# salo_led_pcb.net
KiCad netlist of a schematic drawn in Altium Designer
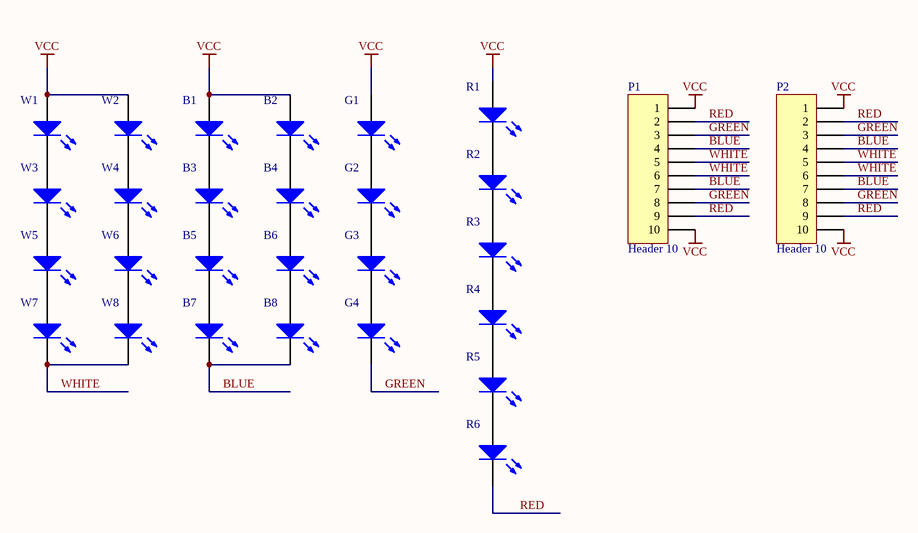
[diagram p0: salo_led_pcb.SchDoc]

(export (version "E")
  (design (tool "Eeschema 10.0.6"))
  (components
    (comp (ref "B1")
      (value "LED0")
      (footprint "1W LED")
      (description "Typical INFRARED GaAs LED")
      (libsource (lib "Miscellaneous Devices") (part "LED0"))
    )
    (comp (ref "B2")
      (value "LED0")
      (footprint "1W LED")
      (description "Typical INFRARED GaAs LED")
      (libsource (lib "Miscellaneous Devices") (part "LED0"))
    )
    (comp (ref "B3")
      (value "LED0")
      (footprint "1W LED")
      (description "Typical INFRARED GaAs LED")
      (libsource (lib "Miscellaneous Devices") (part "LED0"))
    )
    (comp (ref "B4")
      (value "LED0")
      (footprint "1W LED")
      (description "Typical INFRARED GaAs LED")
      (libsource (lib "Miscellaneous Devices") (part "LED0"))
    )
    (comp (ref "B5")
      (value "LED0")
      (footprint "1W LED")
      (description "Typical INFRARED GaAs LED")
      (libsource (lib "Miscellaneous Devices") (part "LED0"))
    )
    (comp (ref "B6")
      (value "LED0")
      (footprint "1W LED")
      (description "Typical INFRARED GaAs LED")
      (libsource (lib "Miscellaneous Devices") (part "LED0"))
    )
    (comp (ref "B7")
      (value "LED0")
      (footprint "1W LED")
      (description "Typical INFRARED GaAs LED")
      (libsource (lib "Miscellaneous Devices") (part "LED0"))
    )
    (comp (ref "B8")
      (value "LED0")
      (footprint "1W LED")
      (description "Typical INFRARED GaAs LED")
      (libsource (lib "Miscellaneous Devices") (part "LED0"))
    )
    (comp (ref "G1")
      (value "LED0")
      (footprint "1W LED")
      (description "Typical INFRARED GaAs LED")
      (libsource (lib "Miscellaneous Devices") (part "LED0"))
    )
    (comp (ref "G2")
      (value "LED0")
      (footprint "1W LED")
      (description "Typical INFRARED GaAs LED")
      (libsource (lib "Miscellaneous Devices") (part "LED0"))
    )
    (comp (ref "G3")
      (value "LED0")
      (footprint "1W LED")
      (description "Typical INFRARED GaAs LED")
      (libsource (lib "Miscellaneous Devices") (part "LED0"))
    )
    (comp (ref "G4")
      (value "LED0")
      (footprint "1W LED")
      (description "Typical INFRARED GaAs LED")
      (libsource (lib "Miscellaneous Devices") (part "LED0"))
    )
    (comp (ref "P1")
      (value "Header 10")
      (footprint "HDR1X10")
      (description "Header, 10-Pin")
      (fields (field (name "PUBLISHER") "Altium Limited"))
      (libsource (lib "Miscellaneous Connectors") (part "Header 10"))
    )
    (comp (ref "P2")
      (value "Header 10")
      (footprint "HDR1X10")
      (description "Header, 10-Pin")
      (fields (field (name "PUBLISHER") "Altium Limited"))
      (libsource (lib "Miscellaneous Connectors") (part "Header 10"))
    )
    (comp (ref "R1")
      (value "LED0")
      (footprint "1W LED")
      (description "Typical INFRARED GaAs LED")
      (libsource (lib "Miscellaneous Devices") (part "LED0"))
    )
    (comp (ref "R2")
      (value "LED0")
      (footprint "1W LED")
      (description "Typical INFRARED GaAs LED")
      (libsource (lib "Miscellaneous Devices") (part "LED0"))
    )
    (comp (ref "R3")
      (value "LED0")
      (footprint "1W LED")
      (description "Typical INFRARED GaAs LED")
      (libsource (lib "Miscellaneous Devices") (part "LED0"))
    )
    (comp (ref "R4")
      (value "LED0")
      (footprint "1W LED")
      (description "Typical INFRARED GaAs LED")
      (libsource (lib "Miscellaneous Devices") (part "LED0"))
    )
    (comp (ref "R5")
      (value "LED0")
      (footprint "1W LED")
      (description "Typical INFRARED GaAs LED")
      (libsource (lib "Miscellaneous Devices") (part "LED0"))
    )
    (comp (ref "R6")
      (value "LED0")
      (footprint "1W LED")
      (description "Typical INFRARED GaAs LED")
      (libsource (lib "Miscellaneous Devices") (part "LED0"))
    )
    (comp (ref "W1")
      (value "LED0")
      (footprint "1W LED")
      (description "Typical INFRARED GaAs LED")
      (libsource (lib "Miscellaneous Devices") (part "LED0"))
    )
    (comp (ref "W2")
      (value "LED0")
      (footprint "1W LED")
      (description "Typical INFRARED GaAs LED")
      (libsource (lib "Miscellaneous Devices") (part "LED0"))
    )
    (comp (ref "W3")
      (value "LED0")
      (footprint "1W LED")
      (description "Typical INFRARED GaAs LED")
      (libsource (lib "Miscellaneous Devices") (part "LED0"))
    )
    (comp (ref "W4")
      (value "LED0")
      (footprint "1W LED")
      (description "Typical INFRARED GaAs LED")
      (libsource (lib "Miscellaneous Devices") (part "LED0"))
    )
    (comp (ref "W5")
      (value "LED0")
      (footprint "1W LED")
      (description "Typical INFRARED GaAs LED")
      (libsource (lib "Miscellaneous Devices") (part "LED0"))
    )
    (comp (ref "W6")
      (value "LED0")
      (footprint "1W LED")
      (description "Typical INFRARED GaAs LED")
      (libsource (lib "Miscellaneous Devices") (part "LED0"))
    )
    (comp (ref "W7")
      (value "LED0")
      (footprint "1W LED")
      (description "Typical INFRARED GaAs LED")
      (libsource (lib "Miscellaneous Devices") (part "LED0"))
    )
    (comp (ref "W8")
      (value "LED0")
      (footprint "1W LED")
      (description "Typical INFRARED GaAs LED")
      (libsource (lib "Miscellaneous Devices") (part "LED0"))
    )
  )
  (nets
    (net (code "1") (name "/BLUE") (class "Default")
      (node (ref "B7") (pin "2") (pinfunction "K_2") (pintype "passive"))
      (node (ref "B8") (pin "2") (pinfunction "K_2") (pintype "passive"))
      (node (ref "P1") (pin "4") (pinfunction "4_4") (pintype "passive"))
      (node (ref "P1") (pin "7") (pinfunction "7_7") (pintype "passive"))
      (node (ref "P2") (pin "4") (pinfunction "4_4") (pintype "passive"))
      (node (ref "P2") (pin "7") (pinfunction "7_7") (pintype "passive"))
    )
    (net (code "2") (name "/GREEN") (class "Default")
      (node (ref "G4") (pin "2") (pinfunction "K_2") (pintype "passive"))
      (node (ref "P1") (pin "3") (pinfunction "3_3") (pintype "passive"))
      (node (ref "P1") (pin "8") (pinfunction "8_8") (pintype "passive"))
      (node (ref "P2") (pin "3") (pinfunction "3_3") (pintype "passive"))
      (node (ref "P2") (pin "8") (pinfunction "8_8") (pintype "passive"))
    )
    (net (code "3") (name "/RED") (class "Default")
      (node (ref "P1") (pin "2") (pinfunction "2_2") (pintype "passive"))
      (node (ref "P1") (pin "9") (pinfunction "9_9") (pintype "passive"))
      (node (ref "P2") (pin "2") (pinfunction "2_2") (pintype "passive"))
      (node (ref "P2") (pin "9") (pinfunction "9_9") (pintype "passive"))
      (node (ref "R6") (pin "2") (pinfunction "K_2") (pintype "passive"))
    )
    (net (code "4") (name "/WHITE") (class "Default")
      (node (ref "P1") (pin "5") (pinfunction "5_5") (pintype "passive"))
      (node (ref "P1") (pin "6") (pinfunction "6_6") (pintype "passive"))
      (node (ref "P2") (pin "5") (pinfunction "5_5") (pintype "passive"))
      (node (ref "P2") (pin "6") (pinfunction "6_6") (pintype "passive"))
      (node (ref "W7") (pin "2") (pinfunction "K_2") (pintype "passive"))
      (node (ref "W8") (pin "2") (pinfunction "K_2") (pintype "passive"))
    )
    (net (code "5") (name "Net-(B1-K)") (class "Default")
      (node (ref "B1") (pin "2") (pinfunction "K_2") (pintype "passive"))
      (node (ref "B3") (pin "1") (pinfunction "A_1") (pintype "passive"))
    )
    (net (code "6") (name "Net-(B2-K)") (class "Default")
      (node (ref "B2") (pin "2") (pinfunction "K_2") (pintype "passive"))
      (node (ref "B4") (pin "1") (pinfunction "A_1") (pintype "passive"))
    )
    (net (code "7") (name "Net-(B3-K)") (class "Default")
      (node (ref "B3") (pin "2") (pinfunction "K_2") (pintype "passive"))
      (node (ref "B5") (pin "1") (pinfunction "A_1") (pintype "passive"))
    )
    (net (code "8") (name "Net-(B4-K)") (class "Default")
      (node (ref "B4") (pin "2") (pinfunction "K_2") (pintype "passive"))
      (node (ref "B6") (pin "1") (pinfunction "A_1") (pintype "passive"))
    )
    (net (code "9") (name "Net-(B5-K)") (class "Default")
      (node (ref "B5") (pin "2") (pinfunction "K_2") (pintype "passive"))
      (node (ref "B7") (pin "1") (pinfunction "A_1") (pintype "passive"))
    )
    (net (code "10") (name "Net-(B6-K)") (class "Default")
      (node (ref "B6") (pin "2") (pinfunction "K_2") (pintype "passive"))
      (node (ref "B8") (pin "1") (pinfunction "A_1") (pintype "passive"))
    )
    (net (code "11") (name "Net-(G1-K)") (class "Default")
      (node (ref "G1") (pin "2") (pinfunction "K_2") (pintype "passive"))
      (node (ref "G2") (pin "1") (pinfunction "A_1") (pintype "passive"))
    )
    (net (code "12") (name "Net-(G2-K)") (class "Default")
      (node (ref "G2") (pin "2") (pinfunction "K_2") (pintype "passive"))
      (node (ref "G3") (pin "1") (pinfunction "A_1") (pintype "passive"))
    )
    (net (code "13") (name "Net-(G3-K)") (class "Default")
      (node (ref "G3") (pin "2") (pinfunction "K_2") (pintype "passive"))
      (node (ref "G4") (pin "1") (pinfunction "A_1") (pintype "passive"))
    )
    (net (code "14") (name "Net-(R1-K)") (class "Default")
      (node (ref "R1") (pin "2") (pinfunction "K_2") (pintype "passive"))
      (node (ref "R2") (pin "1") (pinfunction "A_1") (pintype "passive"))
    )
    (net (code "15") (name "Net-(R2-K)") (class "Default")
      (node (ref "R2") (pin "2") (pinfunction "K_2") (pintype "passive"))
      (node (ref "R3") (pin "1") (pinfunction "A_1") (pintype "passive"))
    )
    (net (code "16") (name "Net-(R3-K)") (class "Default")
      (node (ref "R3") (pin "2") (pinfunction "K_2") (pintype "passive"))
      (node (ref "R4") (pin "1") (pinfunction "A_1") (pintype "passive"))
    )
    (net (code "17") (name "Net-(R4-K)") (class "Default")
      (node (ref "R4") (pin "2") (pinfunction "K_2") (pintype "passive"))
      (node (ref "R5") (pin "1") (pinfunction "A_1") (pintype "passive"))
    )
    (net (code "18") (name "Net-(R5-K)") (class "Default")
      (node (ref "R5") (pin "2") (pinfunction "K_2") (pintype "passive"))
      (node (ref "R6") (pin "1") (pinfunction "A_1") (pintype "passive"))
    )
    (net (code "19") (name "Net-(W1-K)") (class "Default")
      (node (ref "W1") (pin "2") (pinfunction "K_2") (pintype "passive"))
      (node (ref "W3") (pin "1") (pinfunction "A_1") (pintype "passive"))
    )
    (net (code "20") (name "Net-(W2-K)") (class "Default")
      (node (ref "W2") (pin "2") (pinfunction "K_2") (pintype "passive"))
      (node (ref "W4") (pin "1") (pinfunction "A_1") (pintype "passive"))
    )
    (net (code "21") (name "Net-(W3-K)") (class "Default")
      (node (ref "W3") (pin "2") (pinfunction "K_2") (pintype "passive"))
      (node (ref "W5") (pin "1") (pinfunction "A_1") (pintype "passive"))
    )
    (net (code "22") (name "Net-(W4-K)") (class "Default")
      (node (ref "W4") (pin "2") (pinfunction "K_2") (pintype "passive"))
      (node (ref "W6") (pin "1") (pinfunction "A_1") (pintype "passive"))
    )
    (net (code "23") (name "Net-(W5-K)") (class "Default")
      (node (ref "W5") (pin "2") (pinfunction "K_2") (pintype "passive"))
      (node (ref "W7") (pin "1") (pinfunction "A_1") (pintype "passive"))
    )
    (net (code "24") (name "Net-(W6-K)") (class "Default")
      (node (ref "W6") (pin "2") (pinfunction "K_2") (pintype "passive"))
      (node (ref "W8") (pin "1") (pinfunction "A_1") (pintype "passive"))
    )
    (net (code "25") (name "VCC") (class "Default")
      (node (ref "B1") (pin "1") (pinfunction "A_1") (pintype "passive"))
      (node (ref "B2") (pin "1") (pinfunction "A_1") (pintype "passive"))
      (node (ref "G1") (pin "1") (pinfunction "A_1") (pintype "passive"))
      (node (ref "P1") (pin "1") (pinfunction "1_1") (pintype "passive"))
      (node (ref "P1") (pin "10") (pinfunction "10_10") (pintype "passive"))
      (node (ref "P2") (pin "1") (pinfunction "1_1") (pintype "passive"))
      (node (ref "P2") (pin "10") (pinfunction "10_10") (pintype "passive"))
      (node (ref "R1") (pin "1") (pinfunction "A_1") (pintype "passive"))
      (node (ref "W1") (pin "1") (pinfunction "A_1") (pintype "passive"))
      (node (ref "W2") (pin "1") (pinfunction "A_1") (pintype "passive"))
    )
  )
)
